# EvalBoard_SwitchingPS_v0_1a.net
KiCad netlist of a schematic drawn in EAGLE
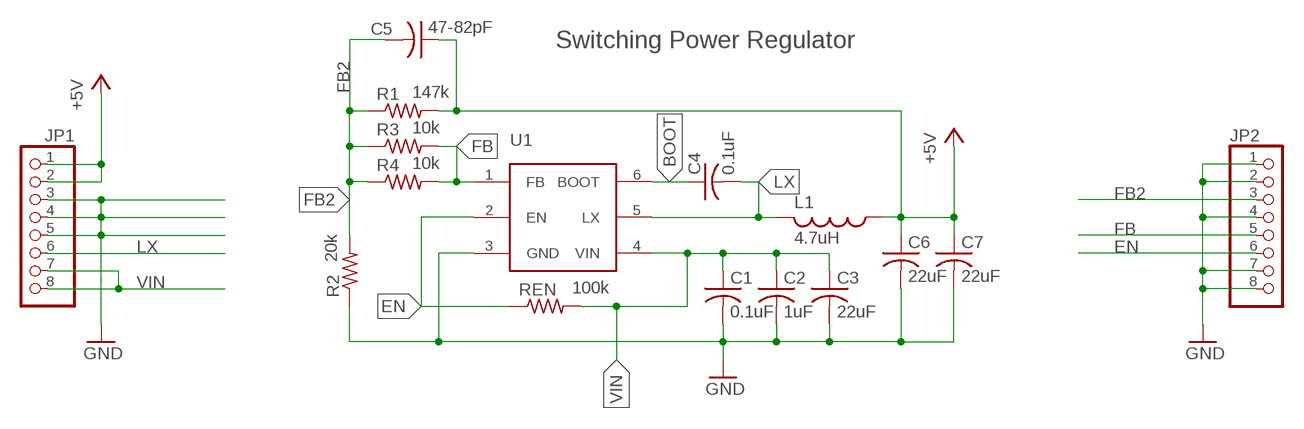
[diagram p0: schematic, sheet 1]

(export (version "E")
  (design (tool "Eeschema 10.0.6"))
  (components
    (comp (ref "C1")
      (value "0.1uF")
      (footprint "eagle-import:C0603")
      (libsource (lib "eagle-import") (part "C-USC0603"))
    )
    (comp (ref "C2")
      (value "1uF")
      (footprint "eagle-import:C0603")
      (libsource (lib "eagle-import") (part "C-USC0603"))
    )
    (comp (ref "C3")
      (value "22uF")
      (footprint "eagle-import:C1206")
      (libsource (lib "eagle-import") (part "C-USC1206"))
    )
    (comp (ref "C4")
      (value "0.1uF")
      (footprint "eagle-import:C0603")
      (libsource (lib "eagle-import") (part "C-USC0603"))
    )
    (comp (ref "C5")
      (value "47-82pF")
      (footprint "eagle-import:C0603")
      (libsource (lib "eagle-import") (part "C-USC0603"))
    )
    (comp (ref "C6")
      (value "22uF")
      (footprint "eagle-import:C1206")
      (libsource (lib "eagle-import") (part "C-USC1206"))
    )
    (comp (ref "C7")
      (value "22uF")
      (footprint "eagle-import:C1206")
      (libsource (lib "eagle-import") (part "C-USC1206"))
    )
    (comp (ref "JP1")
      (value "PINHD-1X8BIG")
      (footprint "eagle-import:1X08-BIG")
      (libsource (lib "eagle-import") (part "PINHD-1X8BIG"))
    )
    (comp (ref "JP2")
      (value "PINHD-1X8BIG")
      (footprint "eagle-import:1X08-BIG")
      (libsource (lib "eagle-import") (part "PINHD-1X8BIG"))
    )
    (comp (ref "L1")
      (value "4.7uH")
      (footprint "eagle-import:0207_15")
      (libsource (lib "eagle-import") (part "L-US0207/15"))
    )
    (comp (ref "R1")
      (value "147k")
      (footprint "eagle-import:R0603")
      (libsource (lib "eagle-import") (part "R-US_R0603"))
    )
    (comp (ref "R2")
      (value "20k")
      (footprint "eagle-import:R0603")
      (libsource (lib "eagle-import") (part "R-US_R0603"))
    )
    (comp (ref "R3")
      (value "10k")
      (footprint "eagle-import:R0603")
      (libsource (lib "eagle-import") (part "R-US_R0603"))
    )
    (comp (ref "R4")
      (value "10k")
      (footprint "eagle-import:R0603")
      (libsource (lib "eagle-import") (part "R-US_R0603"))
    )
    (comp (ref "REN")
      (value "100k")
      (footprint "eagle-import:R0603")
      (libsource (lib "eagle-import") (part "R-US_R0603"))
    )
    (comp (ref "U1")
      (value "RT6255AHGJ6FCT-ND")
      (footprint "eagle-import:SOT-23-6")
      (libsource (lib "eagle-import") (part "RT6255A/B_J6F"))
    )
  )
  (nets
    (net (code "1") (name "+5V") (class "Default")
      (node (ref "C5") (pin "1") (pinfunction "1_1") (pintype "passive"))
      (node (ref "C6") (pin "1") (pinfunction "1_1") (pintype "passive"))
      (node (ref "C7") (pin "1") (pinfunction "1_1") (pintype "passive"))
      (node (ref "JP1") (pin "1") (pinfunction "1_1") (pintype "passive"))
      (node (ref "JP1") (pin "2") (pinfunction "2_2") (pintype "passive"))
      (node (ref "L1") (pin "1") (pinfunction "1_1") (pintype "passive"))
      (node (ref "R1") (pin "2") (pinfunction "2_2") (pintype "passive"))
    )
    (net (code "2") (name "BOOT") (class "Default")
      (node (ref "C4") (pin "1") (pinfunction "1_1") (pintype "passive"))
      (node (ref "U1") (pin "6") (pinfunction "BOOT_6") (pintype "input"))
    )
    (net (code "3") (name "EN") (class "Default")
      (node (ref "JP2") (pin "6") (pinfunction "6_6") (pintype "passive"))
      (node (ref "REN") (pin "1") (pinfunction "1_1") (pintype "passive"))
      (node (ref "U1") (pin "2") (pinfunction "EN_2") (pintype "input"))
    )
    (net (code "4") (name "FB") (class "Default")
      (node (ref "JP2") (pin "5") (pinfunction "5_5") (pintype "passive"))
      (node (ref "R3") (pin "2") (pinfunction "2_2") (pintype "passive"))
      (node (ref "R4") (pin "2") (pinfunction "2_2") (pintype "passive"))
      (node (ref "U1") (pin "1") (pinfunction "FB_1") (pintype "input"))
    )
    (net (code "5") (name "FB2") (class "Default")
      (node (ref "C5") (pin "2") (pinfunction "2_2") (pintype "passive"))
      (node (ref "JP2") (pin "3") (pinfunction "3_3") (pintype "passive"))
      (node (ref "R1") (pin "1") (pinfunction "1_1") (pintype "passive"))
      (node (ref "R2") (pin "2") (pinfunction "2_2") (pintype "passive"))
      (node (ref "R3") (pin "1") (pinfunction "1_1") (pintype "passive"))
      (node (ref "R4") (pin "1") (pinfunction "1_1") (pintype "passive"))
    )
    (net (code "6") (name "GND") (class "Default")
      (node (ref "C1") (pin "2") (pinfunction "2_2") (pintype "passive"))
      (node (ref "C2") (pin "2") (pinfunction "2_2") (pintype "passive"))
      (node (ref "C3") (pin "2") (pinfunction "2_2") (pintype "passive"))
      (node (ref "C6") (pin "2") (pinfunction "2_2") (pintype "passive"))
      (node (ref "C7") (pin "2") (pinfunction "2_2") (pintype "passive"))
      (node (ref "JP1") (pin "3") (pinfunction "3_3") (pintype "passive"))
      (node (ref "JP1") (pin "4") (pinfunction "4_4") (pintype "passive"))
      (node (ref "JP1") (pin "5") (pinfunction "5_5") (pintype "passive"))
      (node (ref "JP2") (pin "1") (pinfunction "1_1") (pintype "passive"))
      (node (ref "JP2") (pin "2") (pinfunction "2_2") (pintype "passive"))
      (node (ref "JP2") (pin "4") (pinfunction "4_4") (pintype "passive"))
      (node (ref "JP2") (pin "7") (pinfunction "7_7") (pintype "passive"))
      (node (ref "JP2") (pin "8") (pinfunction "8_8") (pintype "passive"))
      (node (ref "R2") (pin "1") (pinfunction "1_1") (pintype "passive"))
      (node (ref "U1") (pin "3") (pinfunction "GND_3") (pintype "power_in"))
    )
    (net (code "7") (name "LX") (class "Default")
      (node (ref "C4") (pin "2") (pinfunction "2_2") (pintype "passive"))
      (node (ref "JP1") (pin "6") (pinfunction "6_6") (pintype "passive"))
      (node (ref "L1") (pin "2") (pinfunction "2_2") (pintype "passive"))
      (node (ref "U1") (pin "5") (pinfunction "LX_5") (pintype "input"))
    )
    (net (code "8") (name "VIN") (class "Default")
      (node (ref "C1") (pin "1") (pinfunction "1_1") (pintype "passive"))
      (node (ref "C2") (pin "1") (pinfunction "1_1") (pintype "passive"))
      (node (ref "C3") (pin "1") (pinfunction "1_1") (pintype "passive"))
      (node (ref "JP1") (pin "7") (pinfunction "7_7") (pintype "passive"))
      (node (ref "JP1") (pin "8") (pinfunction "8_8") (pintype "passive"))
      (node (ref "REN") (pin "2") (pinfunction "2_2") (pintype "passive"))
      (node (ref "U1") (pin "4") (pinfunction "VIN_4") (pintype "power_in"))
    )
  )
)
